# ESP32_Module.net
KiCad netlist of a schematic drawn in Altium Designer
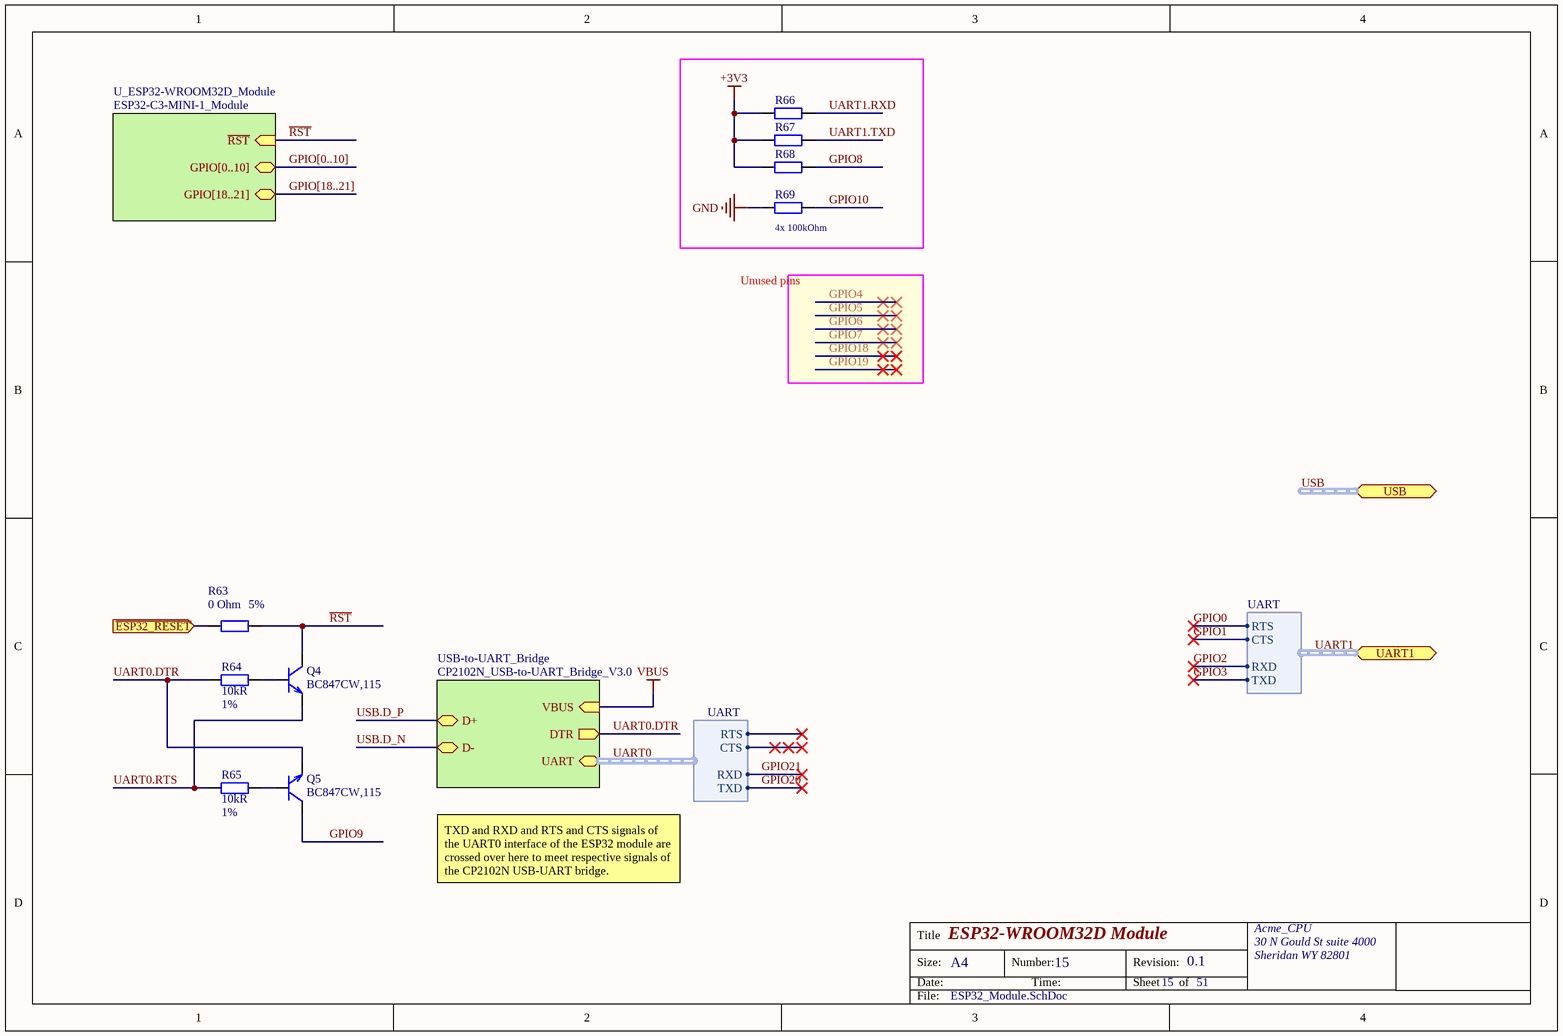
[diagram p0: ESP32_Module.SchDoc]

(export (version "E")
  (design (tool "Eeschema 10.0.6"))
  (components
    (comp (ref "Q4")
      (value "BC847CW,115")
      (footprint "SOT-323")
      (description "Bipolar (BJT) Transistor NPN 45V 100mA 100MHz 200mW Surface Mount SOT-323-3")
      (fields (field (name "MANUFACTURER") "Nexperia"))
      (libsource (lib "bipolar-junction_transistors") (part "TRANS BC847CW,115 NPN 45V 0.1A SOT323"))
    )
    (comp (ref "Q5")
      (value "BC847CW,115")
      (footprint "SOT-323")
      (description "Bipolar (BJT) Transistor NPN 45V 100mA 100MHz 200mW Surface Mount SOT-323-3")
      (fields (field (name "MANUFACTURER") "Nexperia"))
      (libsource (lib "bipolar-junction_transistors") (part "TRANS BC847CW,115 NPN 45V 0.1A SOT323"))
    )
    (comp (ref "R63")
      (value "RES SMD 0 OHM JUMPER 1/16W 0402")
      (footprint "R0402")
      (description "0 Ohms Jumper 0.063W, 1/16W Chip Resistor 0402 (1005 Metric) Moisture Resistant Thick Film")
      (fields
        (field (name "MANUFACTURER") "Yageo")
        (field (name "MANUFACTURER PART NUMBER") "RC0402JR-070RL")
        (field (name "TOLERANCE") "5%")
        (field (name "RESISTANCE") "0 Ohm")
      )
      (libsource (lib "resistors_smd") (part "RES SMD 0 OHM JUMPER 1/16W 0402"))
    )
    (comp (ref "R64")
      (value "RES SMD 10K OHM 1% 1/16W 0402")
      (footprint "R0402")
      (description "10 kOhms ±1% 0.063W, 1/16W Chip Resistor 0402 (1005 Metric) Moisture Resistant Thick Film")
      (fields
        (field (name "MANUFACTURER PART NUMBER") "RC0402FR-0710KP")
        (field (name "MANUFACTURER") "Yageo")
        (field (name "RESISTANCE") "10kR")
        (field (name "TOLERANCE") "1%")
      )
      (libsource (lib "resistors_smd") (part "RES SMD 10K OHM 1% 1/16W 0402"))
    )
    (comp (ref "R65")
      (value "RES SMD 10K OHM 1% 1/16W 0402")
      (footprint "R0402")
      (description "10 kOhms ±1% 0.063W, 1/16W Chip Resistor 0402 (1005 Metric) Moisture Resistant Thick Film")
      (fields
        (field (name "MANUFACTURER PART NUMBER") "RC0402FR-0710KP")
        (field (name "MANUFACTURER") "Yageo")
        (field (name "RESISTANCE") "10kR")
        (field (name "TOLERANCE") "1%")
      )
      (libsource (lib "resistors_smd") (part "RES SMD 10K OHM 1% 1/16W 0402"))
    )
    (comp (ref "R66")
      (value "RES SMD 100K OHM 1% 1/16W 0402")
      (footprint "R0402")
      (description "100 kOhms ±1% 0.063W, 1/16W Chip Resistor 0402 (1005 Metric) Moisture Resistant Thick Film")
      (fields
        (field (name "MANUFACTURER") "Yageo")
        (field (name "MANUFACTURER PART NUMBER") "RC0402FR-07100KL")
      )
      (libsource (lib "resistors_smd") (part "RES SMD 100K OHM 1% 1/16W 0402"))
    )
    (comp (ref "R67")
      (value "RES SMD 100K OHM 1% 1/16W 0402")
      (footprint "R0402")
      (description "100 kOhms ±1% 0.063W, 1/16W Chip Resistor 0402 (1005 Metric) Moisture Resistant Thick Film")
      (fields
        (field (name "MANUFACTURER") "Yageo")
        (field (name "MANUFACTURER PART NUMBER") "RC0402FR-07100KL")
      )
      (libsource (lib "resistors_smd") (part "RES SMD 100K OHM 1% 1/16W 0402"))
    )
    (comp (ref "R68")
      (value "RES SMD 100K OHM 1% 1/16W 0402")
      (footprint "R0402")
      (description "100 kOhms ±1% 0.063W, 1/16W Chip Resistor 0402 (1005 Metric) Moisture Resistant Thick Film")
      (fields
        (field (name "MANUFACTURER") "Yageo")
        (field (name "MANUFACTURER PART NUMBER") "RC0402FR-07100KL")
      )
      (libsource (lib "resistors_smd") (part "RES SMD 100K OHM 1% 1/16W 0402"))
    )
    (comp (ref "R69")
      (value "RES SMD 100K OHM 1% 1/16W 0402")
      (footprint "R0402")
      (description "100 kOhms ±1% 0.063W, 1/16W Chip Resistor 0402 (1005 Metric) Moisture Resistant Thick Film")
      (fields
        (field (name "MANUFACTURER") "Yageo")
        (field (name "MANUFACTURER PART NUMBER") "RC0402FR-07100KL")
      )
      (libsource (lib "resistors_smd") (part "RES SMD 100K OHM 1% 1/16W 0402"))
    )
  )
  (nets
    (net (code "4") (name "+3V3") (class "Default")
      (node (ref "R66") (pin "1") (pinfunction "1_1") (pintype "passive"))
      (node (ref "R67") (pin "1") (pinfunction "1_1") (pintype "passive"))
      (node (ref "R68") (pin "1") (pinfunction "1_1") (pintype "passive"))
    )
    (net (code "5") (name "/ESP32_RESET") (class "Default")
      (node (ref "R63") (pin "1") (pinfunction "1_1") (pintype "passive"))
    )
    (net (code "14") (name "/GPIO8") (class "Default")
      (node (ref "R68") (pin "2") (pinfunction "2_2") (pintype "passive"))
    )
    (net (code "15") (name "/GPIO9") (class "Default")
      (node (ref "Q5") (pin "3") (pinfunction "C_3") (pintype "passive"))
    )
    (net (code "16") (name "/GPIO10") (class "Default")
      (node (ref "R69") (pin "2") (pinfunction "2_2") (pintype "passive"))
    )
    (net (code "23") (name "/RST") (class "Default")
      (node (ref "Q4") (pin "3") (pinfunction "C_3") (pintype "passive"))
      (node (ref "R63") (pin "2") (pinfunction "2_2") (pintype "passive"))
    )
    (net (code "24") (name "/UART0.DTR") (class "Default")
      (node (ref "Q5") (pin "2") (pinfunction "E_2") (pintype "passive"))
      (node (ref "R64") (pin "1") (pinfunction "1_1") (pintype "passive"))
    )
    (net (code "25") (name "/UART0.RTS") (class "Default")
      (node (ref "Q4") (pin "2") (pinfunction "E_2") (pintype "passive"))
      (node (ref "R65") (pin "1") (pinfunction "1_1") (pintype "passive"))
    )
    (net (code "27") (name "/UART1.RXD") (class "Default")
      (node (ref "R66") (pin "2") (pinfunction "2_2") (pintype "passive"))
    )
    (net (code "28") (name "/UART1.TXD") (class "Default")
      (node (ref "R67") (pin "2") (pinfunction "2_2") (pintype "passive"))
    )
    (net (code "33") (name "GND") (class "Default")
      (node (ref "R69") (pin "1") (pinfunction "1_1") (pintype "passive"))
    )
    (net (code "34") (name "Net-(Q4-B)") (class "Default")
      (node (ref "Q4") (pin "1") (pinfunction "B_1") (pintype "passive"))
      (node (ref "R64") (pin "2") (pinfunction "2_2") (pintype "passive"))
    )
    (net (code "35") (name "Net-(Q5-B)") (class "Default")
      (node (ref "Q5") (pin "1") (pinfunction "B_1") (pintype "passive"))
      (node (ref "R65") (pin "2") (pinfunction "2_2") (pintype "passive"))
    )
  )
)
